# RJ45_2.net
KiCad netlist of a schematic drawn in Altium Designer
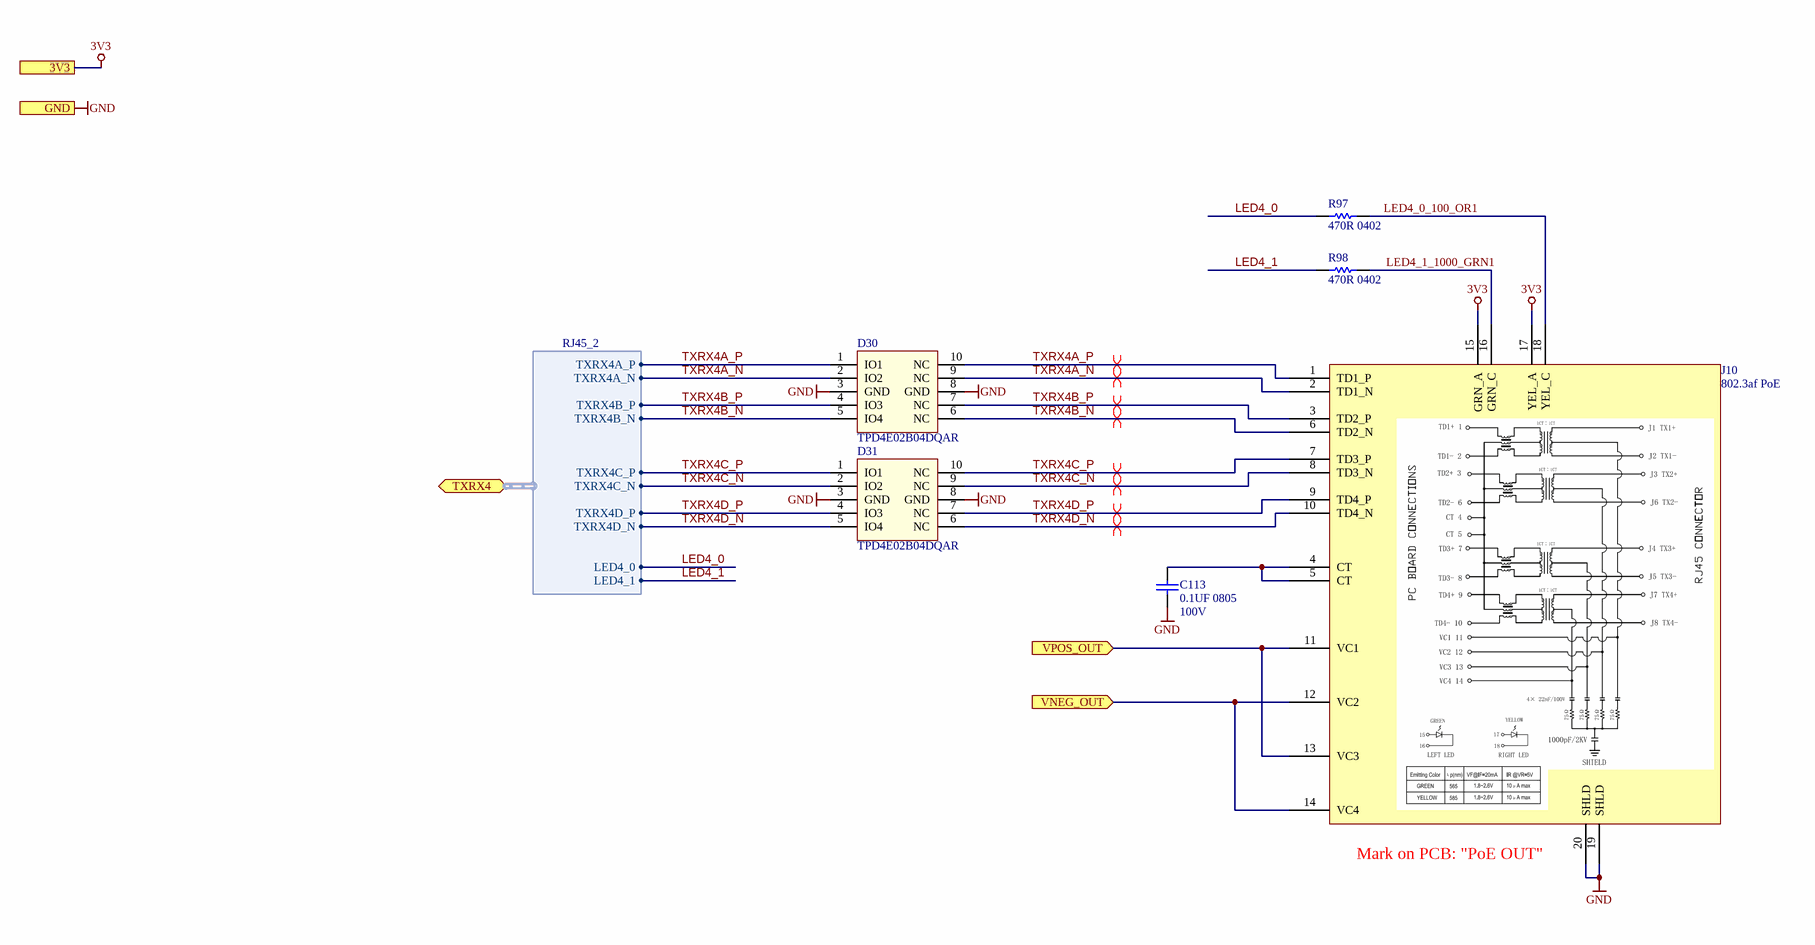
[diagram p0: RJ45_2.SchDoc]

(export (version "E")
  (design (tool "Eeschema 10.0.6"))
  (components
    (comp (ref "C113")
      (value "0.1UF 0805")
      (footprint "CAPC0805(2012)145_N")
      (description "CAP CER 0.1UF 100V X7R 0805")
      (fields (field (name "TOLERANCE") "10%") (field (name "VOLTAGE RATING") "100V"))
      (libsource (lib "PCBProject") (part "CL21B104KCFNNNE"))
    )
    (comp (ref "D30")
      (value "TPD4E02B04DQAR")
      (footprint "TPD4E02B04DQAR")
      (libsource (lib "LuxonisMaster") (part "TPD4E02B04DQAR"))
    )
    (comp (ref "D31")
      (value "TPD4E02B04DQAR")
      (footprint "TPD4E02B04DQAR")
      (libsource (lib "LuxonisMaster") (part "TPD4E02B04DQAR"))
    )
    (comp (ref "J10")
      (value "802.3af PoE")
      (footprint "BW2098POE:TRJG0926HENL")
      (description "CONN MAGJACK 1PORT 1000 BASET")
      (libsource (lib "BW2098POE") (part "TRJG0926HENL"))
    )
    (comp (ref "R97")
      (value "470R 0402")
      (footprint "RESC0402(1005)_N")
      (description "RES SMD 470 OHM 1% 1/16W 0402")
      (fields (field (name "TOLERANCE") "1%"))
      (libsource (lib "LuxonisMaster") (part "CRCW0402470RFKED"))
    )
    (comp (ref "R98")
      (value "470R 0402")
      (footprint "RESC0402(1005)_N")
      (description "RES SMD 470 OHM 1% 1/16W 0402")
      (fields (field (name "TOLERANCE") "1%"))
      (libsource (lib "LuxonisMaster") (part "CRCW0402470RFKED"))
    )
  )
  (nets
    (net (code "2") (name "/LED4_0") (class "Default")
      (node (ref "R97") (pin "1") (pinfunction "1_1") (pintype "passive"))
    )
    (net (code "3") (name "/LED4_0_100_OR1") (class "Default")
      (node (ref "J10") (pin "18") (pinfunction "YEL_C_18") (pintype "passive"))
      (node (ref "R97") (pin "2") (pinfunction "2_2") (pintype "passive"))
    )
    (net (code "4") (name "/LED4_1") (class "Default")
      (node (ref "R98") (pin "1") (pinfunction "1_1") (pintype "passive"))
    )
    (net (code "5") (name "/LED4_1_1000_GRN1") (class "Default")
      (node (ref "J10") (pin "16") (pinfunction "GRN_C_16") (pintype "passive"))
      (node (ref "R98") (pin "2") (pinfunction "2_2") (pintype "passive"))
    )
    (net (code "6") (name "/TXRX4A_N") (class "Default")
      (node (ref "D30") (pin "2") (pinfunction "IO2_2") (pintype "passive"))
      (node (ref "D30") (pin "9") (pinfunction "NC_9") (pintype "passive"))
      (node (ref "J10") (pin "2") (pinfunction "TD1_N_2") (pintype "passive"))
    )
    (net (code "7") (name "/TXRX4A_P") (class "Default")
      (node (ref "D30") (pin "1") (pinfunction "IO1_1") (pintype "passive"))
      (node (ref "D30") (pin "10") (pinfunction "NC_10") (pintype "passive"))
      (node (ref "J10") (pin "1") (pinfunction "TD1_P_1") (pintype "passive"))
    )
    (net (code "8") (name "/TXRX4B_N") (class "Default")
      (node (ref "D30") (pin "5") (pinfunction "IO4_5") (pintype "passive"))
      (node (ref "D30") (pin "6") (pinfunction "NC_6") (pintype "passive"))
      (node (ref "J10") (pin "6") (pinfunction "TD2_N_6") (pintype "passive"))
    )
    (net (code "9") (name "/TXRX4B_P") (class "Default")
      (node (ref "D30") (pin "4") (pinfunction "IO3_4") (pintype "passive"))
      (node (ref "D30") (pin "7") (pinfunction "NC_7") (pintype "passive"))
      (node (ref "J10") (pin "3") (pinfunction "TD2_P_3") (pintype "passive"))
    )
    (net (code "10") (name "/TXRX4C_N") (class "Default")
      (node (ref "D31") (pin "2") (pinfunction "IO2_2") (pintype "passive"))
      (node (ref "D31") (pin "9") (pinfunction "NC_9") (pintype "passive"))
      (node (ref "J10") (pin "8") (pinfunction "TD3_N_8") (pintype "passive"))
    )
    (net (code "11") (name "/TXRX4C_P") (class "Default")
      (node (ref "D31") (pin "1") (pinfunction "IO1_1") (pintype "passive"))
      (node (ref "D31") (pin "10") (pinfunction "NC_10") (pintype "passive"))
      (node (ref "J10") (pin "7") (pinfunction "TD3_P_7") (pintype "passive"))
    )
    (net (code "12") (name "/TXRX4D_N") (class "Default")
      (node (ref "D31") (pin "5") (pinfunction "IO4_5") (pintype "passive"))
      (node (ref "D31") (pin "6") (pinfunction "NC_6") (pintype "passive"))
      (node (ref "J10") (pin "10") (pinfunction "TD4_N_10") (pintype "passive"))
    )
    (net (code "13") (name "/TXRX4D_P") (class "Default")
      (node (ref "D31") (pin "4") (pinfunction "IO3_4") (pintype "passive"))
      (node (ref "D31") (pin "7") (pinfunction "NC_7") (pintype "passive"))
      (node (ref "J10") (pin "9") (pinfunction "TD4_P_9") (pintype "passive"))
    )
    (net (code "14") (name "/VNEG_OUT") (class "Default")
      (node (ref "J10") (pin "12") (pinfunction "VC2_12") (pintype "passive"))
      (node (ref "J10") (pin "14") (pinfunction "VC4_14") (pintype "passive"))
    )
    (net (code "15") (name "/VPOS_OUT") (class "Default")
      (node (ref "J10") (pin "11") (pinfunction "VC1_11") (pintype "passive"))
      (node (ref "J10") (pin "13") (pinfunction "VC3_13") (pintype "passive"))
    )
    (net (code "17") (name "3V3") (class "Default")
      (node (ref "J10") (pin "15") (pinfunction "GRN_A_15") (pintype "passive"))
      (node (ref "J10") (pin "17") (pinfunction "YEL_A_17") (pintype "passive"))
    )
    (net (code "18") (name "GND") (class "Default")
      (node (ref "C113") (pin "1") (pinfunction "1_1") (pintype "passive"))
      (node (ref "D30") (pin "3") (pinfunction "GND_3") (pintype "passive"))
      (node (ref "D30") (pin "8") (pinfunction "GND_8") (pintype "passive"))
      (node (ref "D31") (pin "3") (pinfunction "GND_3") (pintype "passive"))
      (node (ref "D31") (pin "8") (pinfunction "GND_8") (pintype "passive"))
      (node (ref "J10") (pin "19") (pinfunction "SHLD_19") (pintype "passive"))
      (node (ref "J10") (pin "20") (pinfunction "SHLD_20") (pintype "passive"))
    )
    (net (code "19") (name "Net-(C113-Pad2)") (class "Default")
      (node (ref "C113") (pin "2") (pinfunction "2_2") (pintype "passive"))
      (node (ref "J10") (pin "4") (pinfunction "CT_4") (pintype "passive"))
      (node (ref "J10") (pin "5") (pinfunction "CT_5") (pintype "passive"))
    )
  )
)
